# Display.net
KiCad netlist of a schematic drawn in Altium Designer
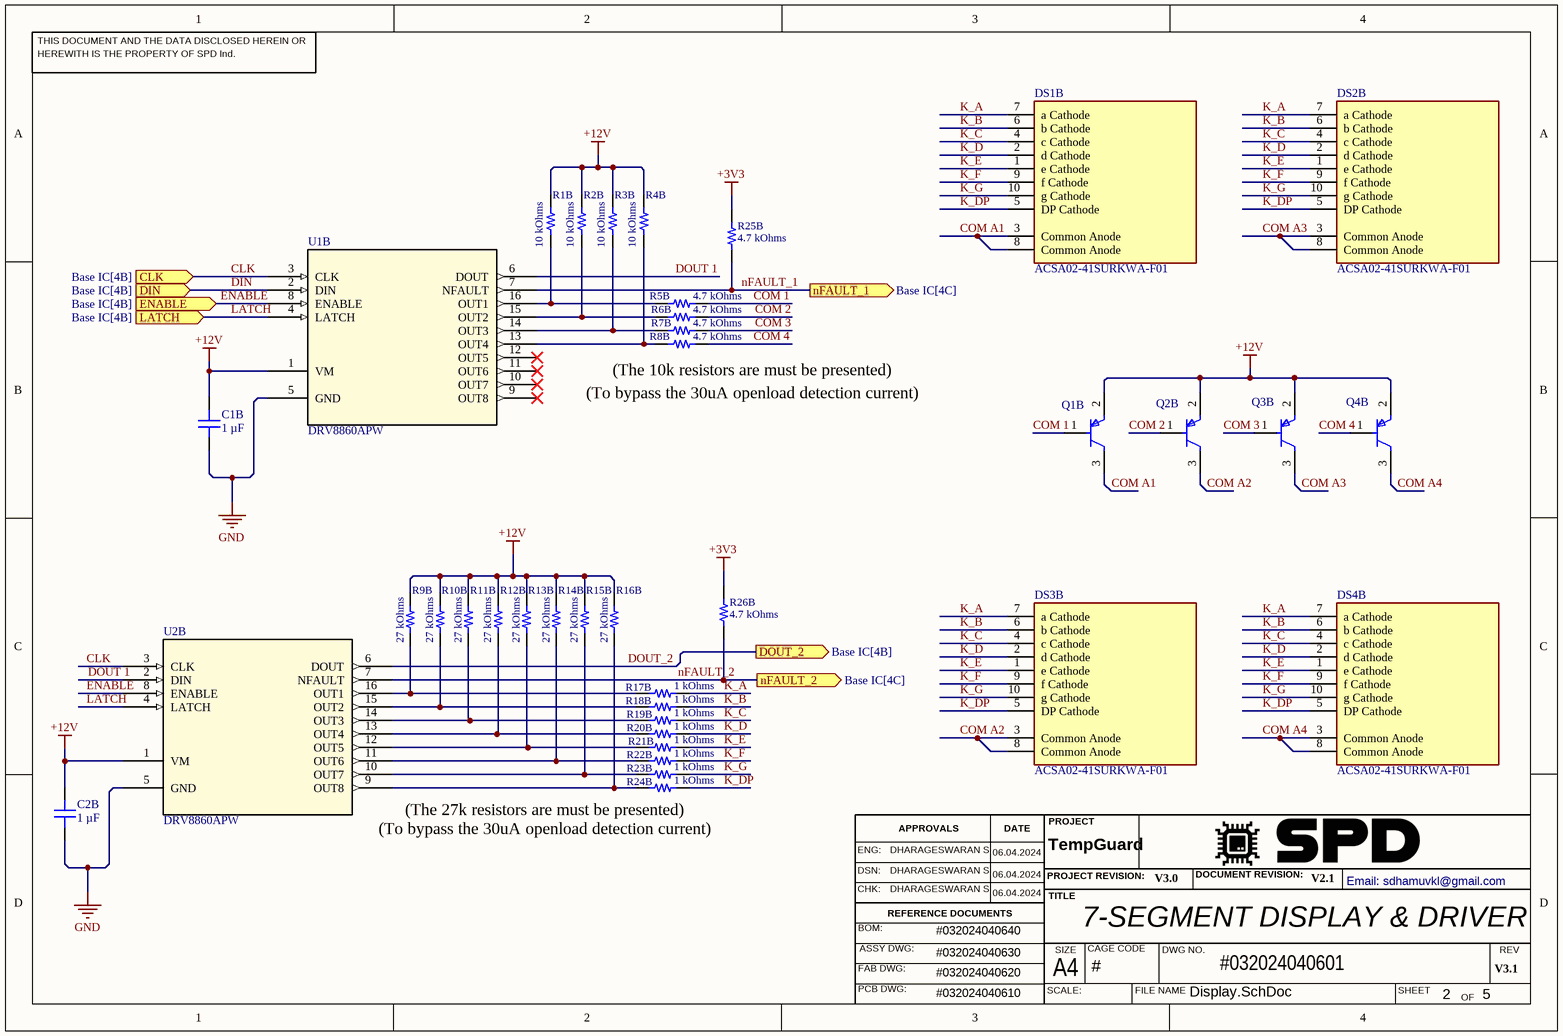
[diagram p0: Display.SchDoc]

(export (version "E")
  (design (tool "Eeschema 10.0.6"))
  (components
    (comp (ref "C1B")
      (value "1 µF")
      (footprint "CAP 0402_1005")
      (description "CAP CER MLCC")
      (fields
        (field (name "PART NUMBER") "GRM155C81C105KE15J")
        (field (name "MANUFACTURER") "Murata Electronics")
      )
      (libsource (lib "Postgres Altium Library - altium_library") (part "Capacitor"))
    )
    (comp (ref "C2B")
      (value "1 µF")
      (footprint "CAP 0402_1005")
      (description "CAP CER MLCC")
      (fields
        (field (name "PART NUMBER") "GRM155C81C105KE15J")
        (field (name "MANUFACTURER") "Murata Electronics")
      )
      (libsource (lib "Postgres Altium Library - altium_library") (part "Capacitor"))
    )
    (comp (ref "DS1B")
      (value "ACSA02-41SURKWA-F01")
      (footprint "FP-ACSA02-41SURKWA-F01-MFG")
      (description "DISPLAY 7-SEG 0.2\" SGL RED 10SMD")
      (libsource (lib "Altium Content Vault") (part "4bb9e92f745044eccd54b42966cc4de"))
    )
    (comp (ref "DS2B")
      (value "ACSA02-41SURKWA-F01")
      (footprint "FP-ACSA02-41SURKWA-F01-MFG")
      (description "DISPLAY 7-SEG 0.2\" SGL RED 10SMD")
      (libsource (lib "Altium Content Vault") (part "4bb9e92f745044eccd54b42966cc4de"))
    )
    (comp (ref "DS3B")
      (value "ACSA02-41SURKWA-F01")
      (footprint "FP-ACSA02-41SURKWA-F01-MFG")
      (description "DISPLAY 7-SEG 0.2\" SGL RED 10SMD")
      (libsource (lib "Altium Content Vault") (part "4bb9e92f745044eccd54b42966cc4de"))
    )
    (comp (ref "DS4B")
      (value "ACSA02-41SURKWA-F01")
      (footprint "FP-ACSA02-41SURKWA-F01-MFG")
      (description "DISPLAY 7-SEG 0.2\" SGL RED 10SMD")
      (libsource (lib "Altium Content Vault") (part "4bb9e92f745044eccd54b42966cc4de"))
    )
    (comp (ref "Q1B")
      (value "MMBT3906FZ-7B")
      (footprint "FP-X2-DFN0606-3-MFG")
      (description "TRANS PNP 40V 0.2A X2-DFN060")
      (libsource (lib "Altium Content Vault") (part "0e8486ed3b47d9c69b8404ba87cf0f7"))
    )
    (comp (ref "Q2B")
      (value "MMBT3906FZ-7B")
      (footprint "FP-X2-DFN0606-3-MFG")
      (description "TRANS PNP 40V 0.2A X2-DFN060")
      (libsource (lib "Altium Content Vault") (part "0e8486ed3b47d9c69b8404ba87cf0f7"))
    )
    (comp (ref "Q3B")
      (value "MMBT3906FZ-7B")
      (footprint "FP-X2-DFN0606-3-MFG")
      (description "TRANS PNP 40V 0.2A X2-DFN060")
      (libsource (lib "Altium Content Vault") (part "0e8486ed3b47d9c69b8404ba87cf0f7"))
    )
    (comp (ref "Q4B")
      (value "MMBT3906FZ-7B")
      (footprint "FP-X2-DFN0606-3-MFG")
      (description "TRANS PNP 40V 0.2A X2-DFN060")
      (libsource (lib "Altium Content Vault") (part "0e8486ed3b47d9c69b8404ba87cf0f7"))
    )
    (comp (ref "R1B")
      (value "10 kOhms")
      (footprint "RES 0402_1005")
      (description "RES SMD 10K OHM 1% 1/16W 0402")
      (fields (field (name "PART NUMBER") "AA0402FR-0710KL") (field (name "TOLERANCE") "±1%"))
      (libsource (lib "Postgres Altium Library - altium_library") (part "Resistor"))
    )
    (comp (ref "R2B")
      (value "10 kOhms")
      (footprint "RES 0402_1005")
      (description "RES SMD 10K OHM 1% 1/16W 0402")
      (fields (field (name "PART NUMBER") "AA0402FR-0710KL") (field (name "TOLERANCE") "±1%"))
      (libsource (lib "Postgres Altium Library - altium_library") (part "Resistor"))
    )
    (comp (ref "R3B")
      (value "10 kOhms")
      (footprint "RES 0402_1005")
      (description "RES SMD 10K OHM 1% 1/16W 0402")
      (fields (field (name "PART NUMBER") "AA0402FR-0710KL") (field (name "TOLERANCE") "±1%"))
      (libsource (lib "Postgres Altium Library - altium_library") (part "Resistor"))
    )
    (comp (ref "R4B")
      (value "10 kOhms")
      (footprint "RES 0402_1005")
      (description "RES SMD 10K OHM 1% 1/16W 0402")
      (fields (field (name "PART NUMBER") "AA0402FR-0710KL") (field (name "TOLERANCE") "±1%"))
      (libsource (lib "Postgres Altium Library - altium_library") (part "Resistor"))
    )
    (comp (ref "R5B")
      (value "4.7 kOhms")
      (footprint "RES 0402_1005")
      (description "RES SMD 4.7K OHM 1% 1/16W 0402")
      (fields (field (name "PART NUMBER") "AC0402FR-074K7L") (field (name "TOLERANCE") "±1%"))
      (libsource (lib "Postgres Altium Library - altium_library") (part "Resistor"))
    )
    (comp (ref "R6B")
      (value "4.7 kOhms")
      (footprint "RES 0402_1005")
      (description "RES SMD 4.7K OHM 1% 1/16W 0402")
      (fields (field (name "PART NUMBER") "AC0402FR-074K7L") (field (name "TOLERANCE") "±1%"))
      (libsource (lib "Postgres Altium Library - altium_library") (part "Resistor"))
    )
    (comp (ref "R7B")
      (value "4.7 kOhms")
      (footprint "RES 0402_1005")
      (description "RES SMD 4.7K OHM 1% 1/16W 0402")
      (fields (field (name "PART NUMBER") "AC0402FR-074K7L") (field (name "TOLERANCE") "±1%"))
      (libsource (lib "Postgres Altium Library - altium_library") (part "Resistor"))
    )
    (comp (ref "R8B")
      (value "4.7 kOhms")
      (footprint "RES 0402_1005")
      (description "RES SMD 4.7K OHM 1% 1/16W 0402")
      (fields (field (name "PART NUMBER") "AC0402FR-074K7L") (field (name "TOLERANCE") "±1%"))
      (libsource (lib "Postgres Altium Library - altium_library") (part "Resistor"))
    )
    (comp (ref "R9B")
      (value "27 kOhms")
      (footprint "RES 0402_1005")
      (description "RES SMD 27K OHM 1% 1/16W 0402")
      (fields (field (name "PART NUMBER") "AC0402FR-0727KL") (field (name "TOLERANCE") "±1%"))
      (libsource (lib "Postgres Altium Library - altium_library") (part "Resistor"))
    )
    (comp (ref "R10B")
      (value "27 kOhms")
      (footprint "RES 0402_1005")
      (description "RES SMD 27K OHM 1% 1/16W 0402")
      (fields (field (name "PART NUMBER") "AC0402FR-0727KL") (field (name "TOLERANCE") "±1%"))
      (libsource (lib "Postgres Altium Library - altium_library") (part "Resistor"))
    )
    (comp (ref "R11B")
      (value "27 kOhms")
      (footprint "RES 0402_1005")
      (description "RES SMD 27K OHM 1% 1/16W 0402")
      (fields (field (name "PART NUMBER") "AC0402FR-0727KL") (field (name "TOLERANCE") "±1%"))
      (libsource (lib "Postgres Altium Library - altium_library") (part "Resistor"))
    )
    (comp (ref "R12B")
      (value "27 kOhms")
      (footprint "RES 0402_1005")
      (description "RES SMD 27K OHM 1% 1/16W 0402")
      (fields (field (name "PART NUMBER") "AC0402FR-0727KL") (field (name "TOLERANCE") "±1%"))
      (libsource (lib "Postgres Altium Library - altium_library") (part "Resistor"))
    )
    (comp (ref "R13B")
      (value "27 kOhms")
      (footprint "RES 0402_1005")
      (description "RES SMD 27K OHM 1% 1/16W 0402")
      (fields (field (name "PART NUMBER") "AC0402FR-0727KL") (field (name "TOLERANCE") "±1%"))
      (libsource (lib "Postgres Altium Library - altium_library") (part "Resistor"))
    )
    (comp (ref "R14B")
      (value "27 kOhms")
      (footprint "RES 0402_1005")
      (description "RES SMD 27K OHM 1% 1/16W 0402")
      (fields (field (name "PART NUMBER") "AC0402FR-0727KL") (field (name "TOLERANCE") "±1%"))
      (libsource (lib "Postgres Altium Library - altium_library") (part "Resistor"))
    )
    (comp (ref "R15B")
      (value "27 kOhms")
      (footprint "RES 0402_1005")
      (description "RES SMD 27K OHM 1% 1/16W 0402")
      (fields (field (name "PART NUMBER") "AC0402FR-0727KL") (field (name "TOLERANCE") "±1%"))
      (libsource (lib "Postgres Altium Library - altium_library") (part "Resistor"))
    )
    (comp (ref "R16B")
      (value "27 kOhms")
      (footprint "RES 0402_1005")
      (description "RES SMD 27K OHM 1% 1/16W 0402")
      (fields (field (name "PART NUMBER") "AC0402FR-0727KL") (field (name "TOLERANCE") "±1%"))
      (libsource (lib "Postgres Altium Library - altium_library") (part "Resistor"))
    )
    (comp (ref "R17B")
      (value "1 kOhms")
      (footprint "RES 0402_1005")
      (description "RES SMD 1K OHM 1% 1/16W 0402")
      (fields (field (name "PART NUMBER") "AA0402FR-071KL") (field (name "TOLERANCE") "±1%"))
      (libsource (lib "Postgres Altium Library - altium_library") (part "Resistor"))
    )
    (comp (ref "R18B")
      (value "1 kOhms")
      (footprint "RES 0402_1005")
      (description "RES SMD 1K OHM 1% 1/16W 0402")
      (fields (field (name "PART NUMBER") "AA0402FR-071KL") (field (name "TOLERANCE") "±1%"))
      (libsource (lib "Postgres Altium Library - altium_library") (part "Resistor"))
    )
    (comp (ref "R19B")
      (value "1 kOhms")
      (footprint "RES 0402_1005")
      (description "RES SMD 1K OHM 1% 1/16W 0402")
      (fields (field (name "PART NUMBER") "AA0402FR-071KL") (field (name "TOLERANCE") "±1%"))
      (libsource (lib "Postgres Altium Library - altium_library") (part "Resistor"))
    )
    (comp (ref "R20B")
      (value "1 kOhms")
      (footprint "RES 0402_1005")
      (description "RES SMD 1K OHM 1% 1/16W 0402")
      (fields (field (name "PART NUMBER") "AA0402FR-071KL") (field (name "TOLERANCE") "±1%"))
      (libsource (lib "Postgres Altium Library - altium_library") (part "Resistor"))
    )
    (comp (ref "R21B")
      (value "1 kOhms")
      (footprint "RES 0402_1005")
      (description "RES SMD 1K OHM 1% 1/16W 0402")
      (fields (field (name "PART NUMBER") "AA0402FR-071KL") (field (name "TOLERANCE") "±1%"))
      (libsource (lib "Postgres Altium Library - altium_library") (part "Resistor"))
    )
    (comp (ref "R22B")
      (value "1 kOhms")
      (footprint "RES 0402_1005")
      (description "RES SMD 1K OHM 1% 1/16W 0402")
      (fields (field (name "PART NUMBER") "AA0402FR-071KL") (field (name "TOLERANCE") "±1%"))
      (libsource (lib "Postgres Altium Library - altium_library") (part "Resistor"))
    )
    (comp (ref "R23B")
      (value "1 kOhms")
      (footprint "RES 0402_1005")
      (description "RES SMD 1K OHM 1% 1/16W 0402")
      (fields (field (name "PART NUMBER") "AA0402FR-071KL") (field (name "TOLERANCE") "±1%"))
      (libsource (lib "Postgres Altium Library - altium_library") (part "Resistor"))
    )
    (comp (ref "R24B")
      (value "1 kOhms")
      (footprint "RES 0402_1005")
      (description "RES SMD 1K OHM 1% 1/16W 0402")
      (fields (field (name "PART NUMBER") "AA0402FR-071KL") (field (name "TOLERANCE") "±1%"))
      (libsource (lib "Postgres Altium Library - altium_library") (part "Resistor"))
    )
    (comp (ref "R25B")
      (value "4.7 kOhms")
      (footprint "RES 0402_1005")
      (description "RES SMD 4.7K OHM 1% 1/16W 0402")
      (fields (field (name "PART NUMBER") "AC0402FR-074K7L") (field (name "TOLERANCE") "±1%"))
      (libsource (lib "Postgres Altium Library - altium_library") (part "Resistor"))
    )
    (comp (ref "R26B")
      (value "4.7 kOhms")
      (footprint "RES 0402_1005")
      (description "RES SMD 4.7K OHM 1% 1/16W 0402")
      (fields (field (name "PART NUMBER") "AC0402FR-074K7L") (field (name "TOLERANCE") "±1%"))
      (libsource (lib "Postgres Altium Library - altium_library") (part "Resistor"))
    )
    (comp (ref "U1B")
      (value "DRV8860APW")
      (footprint "PW_16")
      (description "No Description Available")
      (libsource (lib "DRV8860APW") (part "DRV8860APW"))
    )
    (comp (ref "U2B")
      (value "DRV8860APW")
      (footprint "PW_16")
      (description "No Description Available")
      (libsource (lib "DRV8860APW") (part "DRV8860APW"))
    )
  )
  (nets
    (net (code "1") (name "+3V3") (class "Default")
      (node (ref "R25B") (pin "2") (pinfunction "2_2") (pintype "passive"))
      (node (ref "R26B") (pin "2") (pinfunction "2_2") (pintype "passive"))
    )
    (net (code "2") (name "+12V") (class "Default")
      (node (ref "C1B") (pin "1") (pinfunction "1_1") (pintype "passive"))
      (node (ref "C2B") (pin "1") (pinfunction "1_1") (pintype "passive"))
      (node (ref "Q1B") (pin "2") (pinfunction "E_2") (pintype "passive"))
      (node (ref "Q2B") (pin "2") (pinfunction "E_2") (pintype "passive"))
      (node (ref "Q3B") (pin "2") (pinfunction "E_2") (pintype "passive"))
      (node (ref "Q4B") (pin "2") (pinfunction "E_2") (pintype "passive"))
      (node (ref "R10B") (pin "2") (pinfunction "2_2") (pintype "passive"))
      (node (ref "R11B") (pin "2") (pinfunction "2_2") (pintype "passive"))
      (node (ref "R12B") (pin "2") (pinfunction "2_2") (pintype "passive"))
      (node (ref "R13B") (pin "2") (pinfunction "2_2") (pintype "passive"))
      (node (ref "R14B") (pin "2") (pinfunction "2_2") (pintype "passive"))
      (node (ref "R15B") (pin "2") (pinfunction "2_2") (pintype "passive"))
      (node (ref "R16B") (pin "2") (pinfunction "2_2") (pintype "passive"))
      (node (ref "R1B") (pin "2") (pinfunction "2_2") (pintype "passive"))
      (node (ref "R2B") (pin "2") (pinfunction "2_2") (pintype "passive"))
      (node (ref "R3B") (pin "2") (pinfunction "2_2") (pintype "passive"))
      (node (ref "R4B") (pin "2") (pinfunction "2_2") (pintype "passive"))
      (node (ref "R9B") (pin "2") (pinfunction "2_2") (pintype "passive"))
      (node (ref "U1B") (pin "1") (pinfunction "VM_1") (pintype "power_in"))
      (node (ref "U2B") (pin "1") (pinfunction "VM_1") (pintype "power_in"))
    )
    (net (code "3") (name "/CLK") (class "Default")
      (node (ref "U1B") (pin "3") (pinfunction "CLK_3") (pintype "input"))
      (node (ref "U2B") (pin "3") (pinfunction "CLK_3") (pintype "input"))
    )
    (net (code "4") (name "/COM 1") (class "Default")
      (node (ref "Q1B") (pin "1") (pinfunction "B_1") (pintype "passive"))
      (node (ref "R5B") (pin "2") (pinfunction "2_2") (pintype "passive"))
    )
    (net (code "5") (name "/COM 2") (class "Default")
      (node (ref "Q2B") (pin "1") (pinfunction "B_1") (pintype "passive"))
      (node (ref "R6B") (pin "2") (pinfunction "2_2") (pintype "passive"))
    )
    (net (code "6") (name "/COM 3") (class "Default")
      (node (ref "Q3B") (pin "1") (pinfunction "B_1") (pintype "passive"))
      (node (ref "R7B") (pin "2") (pinfunction "2_2") (pintype "passive"))
    )
    (net (code "7") (name "/COM 4") (class "Default")
      (node (ref "Q4B") (pin "1") (pinfunction "B_1") (pintype "passive"))
      (node (ref "R8B") (pin "2") (pinfunction "2_2") (pintype "passive"))
    )
    (net (code "8") (name "/COM A1") (class "Default")
      (node (ref "DS1B") (pin "3") (pinfunction "Common_Anode_3") (pintype "passive"))
      (node (ref "DS1B") (pin "8") (pinfunction "Common_Anode_8") (pintype "passive"))
      (node (ref "Q1B") (pin "3") (pinfunction "C_3") (pintype "passive"))
    )
    (net (code "9") (name "/COM A2") (class "Default")
      (node (ref "DS3B") (pin "3") (pinfunction "Common_Anode_3") (pintype "passive"))
      (node (ref "DS3B") (pin "8") (pinfunction "Common_Anode_8") (pintype "passive"))
      (node (ref "Q2B") (pin "3") (pinfunction "C_3") (pintype "passive"))
    )
    (net (code "10") (name "/COM A3") (class "Default")
      (node (ref "DS2B") (pin "3") (pinfunction "Common_Anode_3") (pintype "passive"))
      (node (ref "DS2B") (pin "8") (pinfunction "Common_Anode_8") (pintype "passive"))
      (node (ref "Q3B") (pin "3") (pinfunction "C_3") (pintype "passive"))
    )
    (net (code "11") (name "/COM A4") (class "Default")
      (node (ref "DS4B") (pin "3") (pinfunction "Common_Anode_3") (pintype "passive"))
      (node (ref "DS4B") (pin "8") (pinfunction "Common_Anode_8") (pintype "passive"))
      (node (ref "Q4B") (pin "3") (pinfunction "C_3") (pintype "passive"))
    )
    (net (code "12") (name "/DIN") (class "Default")
      (node (ref "U1B") (pin "2") (pinfunction "DIN_2") (pintype "input"))
    )
    (net (code "13") (name "/DOUT 1") (class "Default")
      (node (ref "U1B") (pin "6") (pinfunction "DOUT_6") (pintype "output"))
      (node (ref "U2B") (pin "2") (pinfunction "DIN_2") (pintype "input"))
    )
    (net (code "14") (name "/DOUT_2") (class "Default")
      (node (ref "U2B") (pin "6") (pinfunction "DOUT_6") (pintype "output"))
    )
    (net (code "15") (name "/ENABLE") (class "Default")
      (node (ref "U1B") (pin "8") (pinfunction "ENABLE_8") (pintype "input"))
      (node (ref "U2B") (pin "8") (pinfunction "ENABLE_8") (pintype "input"))
    )
    (net (code "16") (name "/K_A") (class "Default")
      (node (ref "DS1B") (pin "7") (pinfunction "a_Cathode_7") (pintype "passive"))
      (node (ref "DS2B") (pin "7") (pinfunction "a_Cathode_7") (pintype "passive"))
      (node (ref "DS3B") (pin "7") (pinfunction "a_Cathode_7") (pintype "passive"))
      (node (ref "DS4B") (pin "7") (pinfunction "a_Cathode_7") (pintype "passive"))
      (node (ref "R17B") (pin "2") (pinfunction "2_2") (pintype "passive"))
    )
    (net (code "17") (name "/K_B") (class "Default")
      (node (ref "DS1B") (pin "6") (pinfunction "b_Cathode_6") (pintype "passive"))
      (node (ref "DS2B") (pin "6") (pinfunction "b_Cathode_6") (pintype "passive"))
      (node (ref "DS3B") (pin "6") (pinfunction "b_Cathode_6") (pintype "passive"))
      (node (ref "DS4B") (pin "6") (pinfunction "b_Cathode_6") (pintype "passive"))
      (node (ref "R18B") (pin "2") (pinfunction "2_2") (pintype "passive"))
    )
    (net (code "18") (name "/K_C") (class "Default")
      (node (ref "DS1B") (pin "4") (pinfunction "c_Cathode_4") (pintype "passive"))
      (node (ref "DS2B") (pin "4") (pinfunction "c_Cathode_4") (pintype "passive"))
      (node (ref "DS3B") (pin "4") (pinfunction "c_Cathode_4") (pintype "passive"))
      (node (ref "DS4B") (pin "4") (pinfunction "c_Cathode_4") (pintype "passive"))
      (node (ref "R19B") (pin "2") (pinfunction "2_2") (pintype "passive"))
    )
    (net (code "19") (name "/K_D") (class "Default")
      (node (ref "DS1B") (pin "2") (pinfunction "d_Cathode_2") (pintype "passive"))
      (node (ref "DS2B") (pin "2") (pinfunction "d_Cathode_2") (pintype "passive"))
      (node (ref "DS3B") (pin "2") (pinfunction "d_Cathode_2") (pintype "passive"))
      (node (ref "DS4B") (pin "2") (pinfunction "d_Cathode_2") (pintype "passive"))
      (node (ref "R20B") (pin "2") (pinfunction "2_2") (pintype "passive"))
    )
    (net (code "20") (name "/K_DP") (class "Default")
      (node (ref "DS1B") (pin "5") (pinfunction "DP_Cathode_5") (pintype "passive"))
      (node (ref "DS2B") (pin "5") (pinfunction "DP_Cathode_5") (pintype "passive"))
      (node (ref "DS3B") (pin "5") (pinfunction "DP_Cathode_5") (pintype "passive"))
      (node (ref "DS4B") (pin "5") (pinfunction "DP_Cathode_5") (pintype "passive"))
      (node (ref "R24B") (pin "2") (pinfunction "2_2") (pintype "passive"))
    )
    (net (code "21") (name "/K_E") (class "Default")
      (node (ref "DS1B") (pin "1") (pinfunction "e_Cathode_1") (pintype "passive"))
      (node (ref "DS2B") (pin "1") (pinfunction "e_Cathode_1") (pintype "passive"))
      (node (ref "DS3B") (pin "1") (pinfunction "e_Cathode_1") (pintype "passive"))
      (node (ref "DS4B") (pin "1") (pinfunction "e_Cathode_1") (pintype "passive"))
      (node (ref "R21B") (pin "2") (pinfunction "2_2") (pintype "passive"))
    )
    (net (code "22") (name "/K_F") (class "Default")
      (node (ref "DS1B") (pin "9") (pinfunction "f_Cathode_9") (pintype "passive"))
      (node (ref "DS2B") (pin "9") (pinfunction "f_Cathode_9") (pintype "passive"))
      (node (ref "DS3B") (pin "9") (pinfunction "f_Cathode_9") (pintype "passive"))
      (node (ref "DS4B") (pin "9") (pinfunction "f_Cathode_9") (pintype "passive"))
      (node (ref "R22B") (pin "2") (pinfunction "2_2") (pintype "passive"))
    )
    (net (code "23") (name "/K_G") (class "Default")
      (node (ref "DS1B") (pin "10") (pinfunction "g_Cathode_10") (pintype "passive"))
      (node (ref "DS2B") (pin "10") (pinfunction "g_Cathode_10") (pintype "passive"))
      (node (ref "DS3B") (pin "10") (pinfunction "g_Cathode_10") (pintype "passive"))
      (node (ref "DS4B") (pin "10") (pinfunction "g_Cathode_10") (pintype "passive"))
      (node (ref "R23B") (pin "2") (pinfunction "2_2") (pintype "passive"))
    )
    (net (code "24") (name "/LATCH") (class "Default")
      (node (ref "U1B") (pin "4") (pinfunction "LATCH_4") (pintype "input"))
      (node (ref "U2B") (pin "4") (pinfunction "LATCH_4") (pintype "input"))
    )
    (net (code "25") (name "/nFAULT_1") (class "Default")
      (node (ref "R25B") (pin "1") (pinfunction "1_1") (pintype "passive"))
      (node (ref "U1B") (pin "7") (pinfunction "NFAULT_7") (pintype "output"))
    )
    (net (code "26") (name "/nFAULT_2") (class "Default")
      (node (ref "R26B") (pin "1") (pinfunction "1_1") (pintype "passive"))
      (node (ref "U2B") (pin "7") (pinfunction "NFAULT_7") (pintype "output"))
    )
    (net (code "27") (name "GND") (class "Default")
      (node (ref "C1B") (pin "2") (pinfunction "2_2") (pintype "passive"))
      (node (ref "C2B") (pin "2") (pinfunction "2_2") (pintype "passive"))
      (node (ref "U1B") (pin "5") (pinfunction "GND_5") (pintype "power_in"))
      (node (ref "U2B") (pin "5") (pinfunction "GND_5") (pintype "power_in"))
    )
    (net (code "28") (name "Net-(U1B-OUT1)") (class "Default")
      (node (ref "R1B") (pin "1") (pinfunction "1_1") (pintype "passive"))
      (node (ref "R5B") (pin "1") (pinfunction "1_1") (pintype "passive"))
      (node (ref "U1B") (pin "16") (pinfunction "OUT1_16") (pintype "output"))
    )
    (net (code "29") (name "Net-(U1B-OUT2)") (class "Default")
      (node (ref "R2B") (pin "1") (pinfunction "1_1") (pintype "passive"))
      (node (ref "R6B") (pin "1") (pinfunction "1_1") (pintype "passive"))
      (node (ref "U1B") (pin "15") (pinfunction "OUT2_15") (pintype "output"))
    )
    (net (code "30") (name "Net-(U1B-OUT3)") (class "Default")
      (node (ref "R3B") (pin "1") (pinfunction "1_1") (pintype "passive"))
      (node (ref "R7B") (pin "1") (pinfunction "1_1") (pintype "passive"))
      (node (ref "U1B") (pin "14") (pinfunction "OUT3_14") (pintype "output"))
    )
    (net (code "31") (name "Net-(U1B-OUT4)") (class "Default")
      (node (ref "R4B") (pin "1") (pinfunction "1_1") (pintype "passive"))
      (node (ref "R8B") (pin "1") (pinfunction "1_1") (pintype "passive"))
      (node (ref "U1B") (pin "13") (pinfunction "OUT4_13") (pintype "output"))
    )
    (net (code "32") (name "Net-(U2B-OUT1)") (class "Default")
      (node (ref "R17B") (pin "1") (pinfunction "1_1") (pintype "passive"))
      (node (ref "R9B") (pin "1") (pinfunction "1_1") (pintype "passive"))
      (node (ref "U2B") (pin "16") (pinfunction "OUT1_16") (pintype "output"))
    )
    (net (code "33") (name "Net-(U2B-OUT2)") (class "Default")
      (node (ref "R10B") (pin "1") (pinfunction "1_1") (pintype "passive"))
      (node (ref "R18B") (pin "1") (pinfunction "1_1") (pintype "passive"))
      (node (ref "U2B") (pin "15") (pinfunction "OUT2_15") (pintype "output"))
    )
    (net (code "34") (name "Net-(U2B-OUT3)") (class "Default")
      (node (ref "R11B") (pin "1") (pinfunction "1_1") (pintype "passive"))
      (node (ref "R19B") (pin "1") (pinfunction "1_1") (pintype "passive"))
      (node (ref "U2B") (pin "14") (pinfunction "OUT3_14") (pintype "output"))
    )
    (net (code "35") (name "Net-(U2B-OUT4)") (class "Default")
      (node (ref "R12B") (pin "1") (pinfunction "1_1") (pintype "passive"))
      (node (ref "R20B") (pin "1") (pinfunction "1_1") (pintype "passive"))
      (node (ref "U2B") (pin "13") (pinfunction "OUT4_13") (pintype "output"))
    )
    (net (code "36") (name "Net-(U2B-OUT5)") (class "Default")
      (node (ref "R13B") (pin "1") (pinfunction "1_1") (pintype "passive"))
      (node (ref "R21B") (pin "1") (pinfunction "1_1") (pintype "passive"))
      (node (ref "U2B") (pin "12") (pinfunction "OUT5_12") (pintype "output"))
    )
    (net (code "37") (name "Net-(U2B-OUT6)") (class "Default")
      (node (ref "R14B") (pin "1") (pinfunction "1_1") (pintype "passive"))
      (node (ref "R22B") (pin "1") (pinfunction "1_1") (pintype "passive"))
      (node (ref "U2B") (pin "11") (pinfunction "OUT6_11") (pintype "output"))
    )
    (net (code "38") (name "Net-(U2B-OUT7)") (class "Default")
      (node (ref "R15B") (pin "1") (pinfunction "1_1") (pintype "passive"))
      (node (ref "R23B") (pin "1") (pinfunction "1_1") (pintype "passive"))
      (node (ref "U2B") (pin "10") (pinfunction "OUT7_10") (pintype "output"))
    )
    (net (code "39") (name "Net-(U2B-OUT8)") (class "Default")
      (node (ref "R16B") (pin "1") (pinfunction "1_1") (pintype "passive"))
      (node (ref "R24B") (pin "1") (pinfunction "1_1") (pintype "passive"))
      (node (ref "U2B") (pin "9") (pinfunction "OUT8_9") (pintype "output"))
    )
    (net (code "40") (name "unconnected-(U1B-OUT5-Pad12)") (class "Default")
      (node (ref "U1B") (pin "12") (pinfunction "OUT5_12") (pintype "output+no_connect"))
    )
    (net (code "41") (name "unconnected-(U1B-OUT6-Pad11)") (class "Default")
      (node (ref "U1B") (pin "11") (pinfunction "OUT6_11") (pintype "output+no_connect"))
    )
    (net (code "42") (name "unconnected-(U1B-OUT7-Pad10)") (class "Default")
      (node (ref "U1B") (pin "10") (pinfunction "OUT7_10") (pintype "output+no_connect"))
    )
    (net (code "43") (name "unconnected-(U1B-OUT8-Pad9)") (class "Default")
      (node (ref "U1B") (pin "9") (pinfunction "OUT8_9") (pintype "output+no_connect"))
    )
  )
)
